# 5VPowerBoard.net
KiCad netlist of a schematic drawn in EAGLE
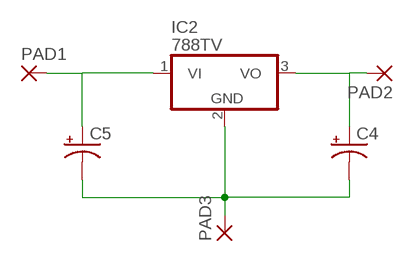
[diagram p0: schematic, sheet 1]

(export (version "E")
  (design (tool "Eeschema 10.0.6"))
  (components
    (comp (ref "C4")
      (value "CPOL-USE2.5-7")
      (footprint "eagle-import:E2,5-7")
      (libsource (lib "eagle-import") (part "CPOL-USE2.5-7"))
    )
    (comp (ref "C5")
      (value "CPOL-USE2.5-7")
      (footprint "eagle-import:E2,5-7")
      (libsource (lib "eagle-import") (part "CPOL-USE2.5-7"))
    )
    (comp (ref "IC2")
      (value "788TV")
      (footprint "eagle-import:TO220V")
      (libsource (lib "eagle-import") (part "78TV8"))
    )
    (comp (ref "PAD1")
      (value "3,81/1,4")
      (footprint "eagle-import:3,81_1,4")
      (libsource (lib "eagle-import") (part "3,81/1,4"))
    )
    (comp (ref "PAD2")
      (value "3,81/1,4")
      (footprint "eagle-import:3,81_1,4")
      (libsource (lib "eagle-import") (part "3,81/1,4"))
    )
    (comp (ref "PAD3")
      (value "3,81/1,4")
      (footprint "eagle-import:3,81_1,4")
      (libsource (lib "eagle-import") (part "3,81/1,4"))
    )
  )
  (nets
    (net (code "1") (name "Net-(IC2-GND)") (class "Default")
      (node (ref "C4") (pin "-") (pinfunction "-_-") (pintype "passive"))
      (node (ref "C5") (pin "-") (pinfunction "-_-") (pintype "passive"))
      (node (ref "IC2") (pin "2") (pinfunction "GND_2") (pintype "passive"))
      (node (ref "PAD3") (pin "1") (pinfunction "P_1") (pintype "passive"))
    )
    (net (code "2") (name "Net-(IC2-VI)") (class "Default")
      (node (ref "C5") (pin "+") (pinfunction "+_+") (pintype "passive"))
      (node (ref "IC2") (pin "1") (pinfunction "VI_1") (pintype "input"))
      (node (ref "PAD1") (pin "1") (pinfunction "P_1") (pintype "passive"))
    )
    (net (code "3") (name "Net-(IC2-VO)") (class "Default")
      (node (ref "C4") (pin "+") (pinfunction "+_+") (pintype "passive"))
      (node (ref "IC2") (pin "3") (pinfunction "VO_3") (pintype "passive"))
      (node (ref "PAD2") (pin "1") (pinfunction "P_1") (pintype "passive"))
    )
  )
)
